# RoboCore_Light_sensor_bar.net
KiCad netlist of a schematic drawn in EAGLE
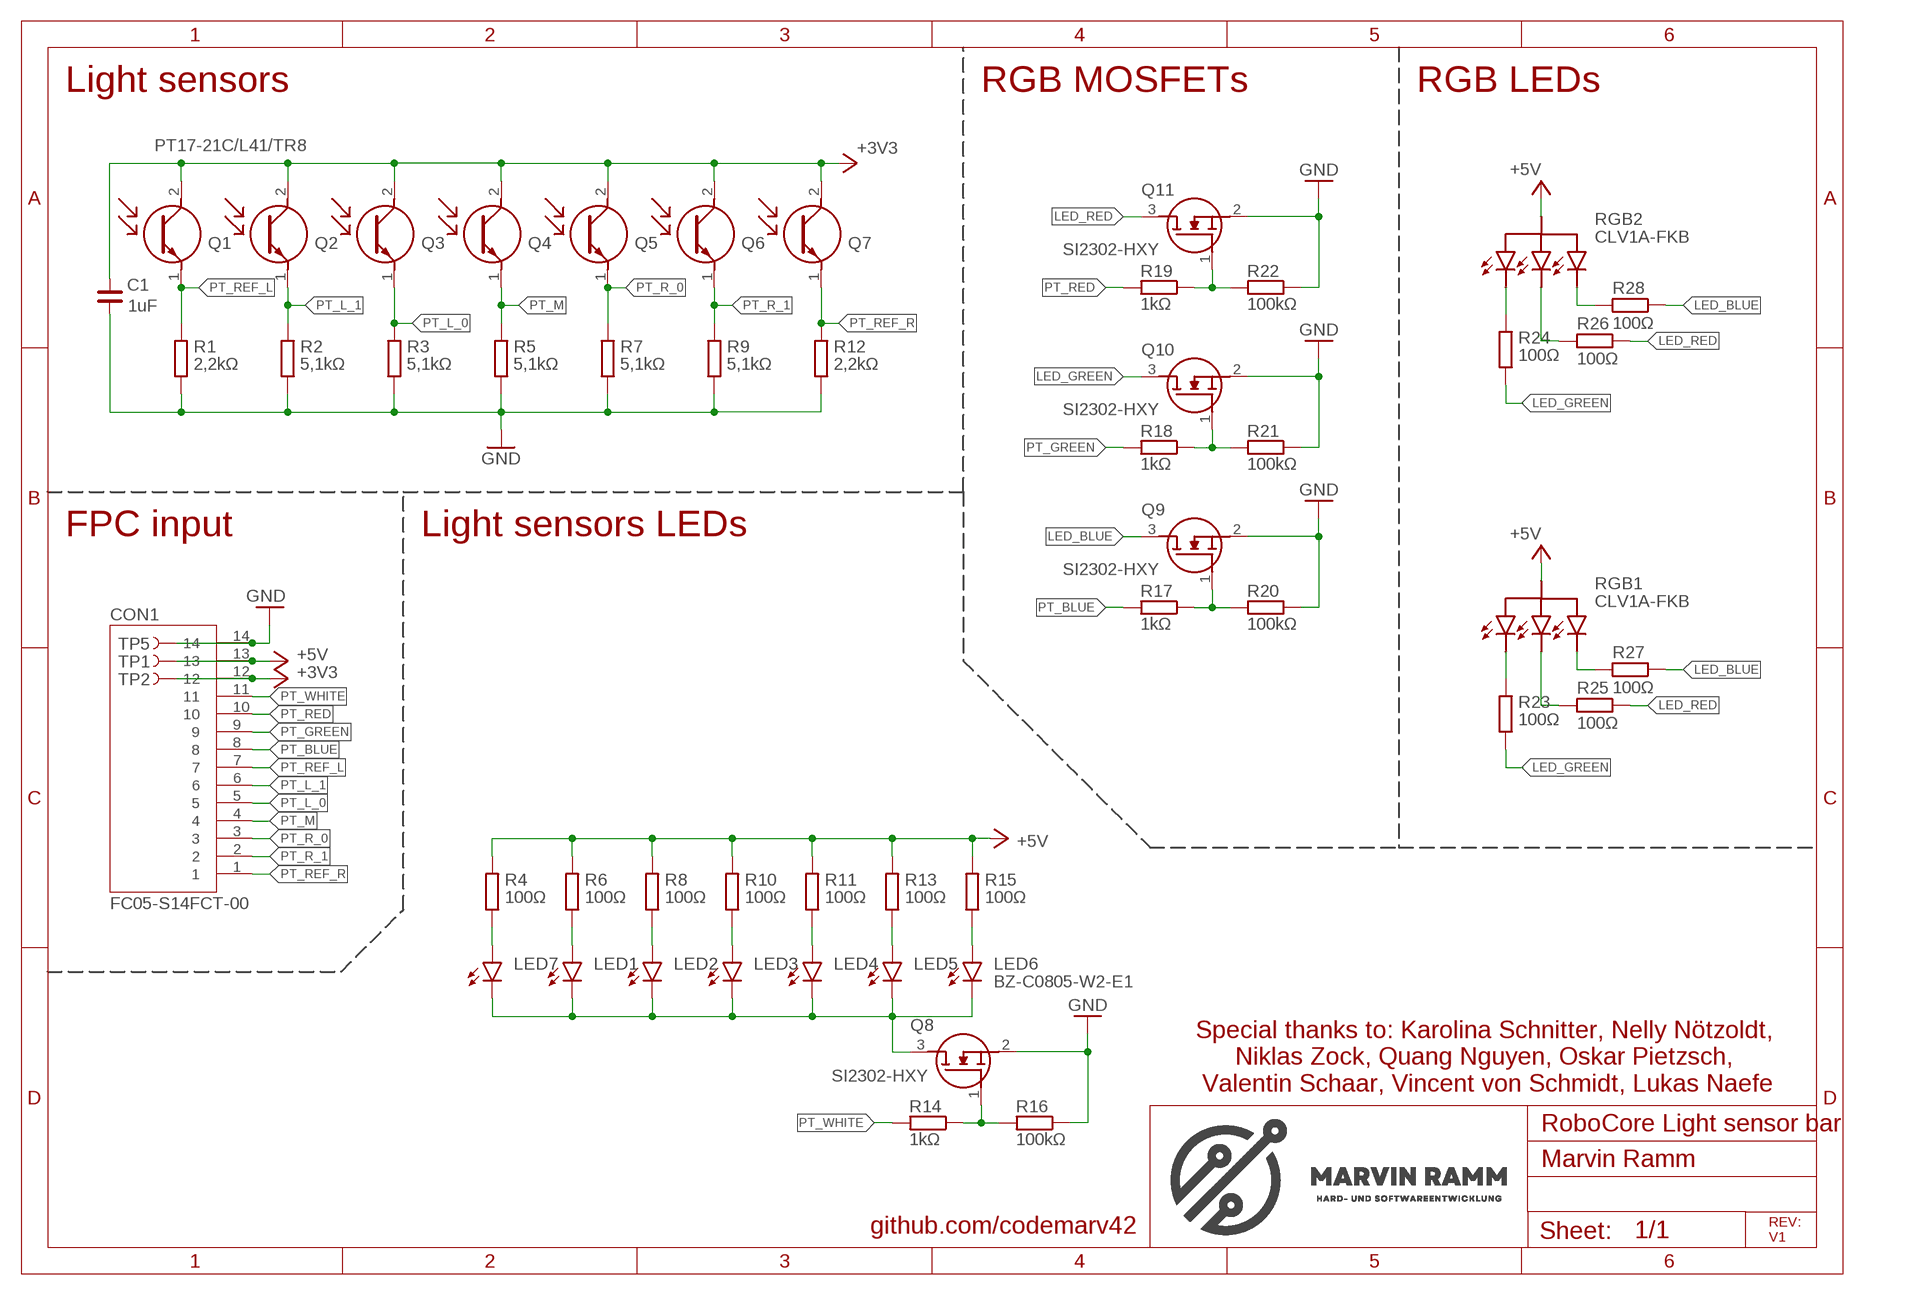
[diagram p0: schematic, sheet 1]

(export (version "E")
  (design (tool "Eeschema 10.0.6"))
  (components
    (comp (ref "C1")
      (value "1uF")
      (footprint "eagle-import:C0402")
      (libsource (lib "eagle-import") (part "C_0402"))
    )
    (comp (ref "CON1")
      (value "FC05-S14FCT-00")
      (footprint "eagle-import:FC05-S14FCT-00")
      (libsource (lib "eagle-import") (part "FC05-S14FCT-00"))
    )
    (comp (ref "LED1")
      (value "LEDCHIP-LED0805")
      (footprint "eagle-import:CHIP-LED0805")
      (libsource (lib "eagle-import") (part "LEDCHIP-LED0805"))
    )
    (comp (ref "LED2")
      (value "LEDCHIP-LED0805")
      (footprint "eagle-import:CHIP-LED0805")
      (libsource (lib "eagle-import") (part "LEDCHIP-LED0805"))
    )
    (comp (ref "LED3")
      (value "LEDCHIP-LED0805")
      (footprint "eagle-import:CHIP-LED0805")
      (libsource (lib "eagle-import") (part "LEDCHIP-LED0805"))
    )
    (comp (ref "LED4")
      (value "LEDCHIP-LED0805")
      (footprint "eagle-import:CHIP-LED0805")
      (libsource (lib "eagle-import") (part "LEDCHIP-LED0805"))
    )
    (comp (ref "LED5")
      (value "LEDCHIP-LED0805")
      (footprint "eagle-import:CHIP-LED0805")
      (libsource (lib "eagle-import") (part "LEDCHIP-LED0805"))
    )
    (comp (ref "LED6")
      (value "LEDCHIP-LED0805")
      (footprint "eagle-import:CHIP-LED0805")
      (libsource (lib "eagle-import") (part "LEDCHIP-LED0805"))
    )
    (comp (ref "LED7")
      (value "LEDCHIP-LED0805")
      (footprint "eagle-import:CHIP-LED0805")
      (libsource (lib "eagle-import") (part "LEDCHIP-LED0805"))
    )
    (comp (ref "Q1")
      (value "PT17-21C/L41/TR8")
      (footprint "eagle-import:0805")
      (libsource (lib "eagle-import") (part "PT17-21C/L41/TR8"))
    )
    (comp (ref "Q2")
      (value "PT17-21C/L41/TR8")
      (footprint "eagle-import:0805")
      (libsource (lib "eagle-import") (part "PT17-21C/L41/TR8"))
    )
    (comp (ref "Q3")
      (value "PT17-21C/L41/TR8")
      (footprint "eagle-import:0805")
      (libsource (lib "eagle-import") (part "PT17-21C/L41/TR8"))
    )
    (comp (ref "Q4")
      (value "PT17-21C/L41/TR8")
      (footprint "eagle-import:0805")
      (libsource (lib "eagle-import") (part "PT17-21C/L41/TR8"))
    )
    (comp (ref "Q5")
      (value "PT17-21C/L41/TR8")
      (footprint "eagle-import:0805")
      (libsource (lib "eagle-import") (part "PT17-21C/L41/TR8"))
    )
    (comp (ref "Q6")
      (value "PT17-21C/L41/TR8")
      (footprint "eagle-import:0805")
      (libsource (lib "eagle-import") (part "PT17-21C/L41/TR8"))
    )
    (comp (ref "Q7")
      (value "PT17-21C/L41/TR8")
      (footprint "eagle-import:0805")
      (libsource (lib "eagle-import") (part "PT17-21C/L41/TR8"))
    )
    (comp (ref "Q8")
      (value "SI2302DDS-T1-GE3")
      (footprint "eagle-import:SOT95P237X112-3N")
      (fields (field (name "MOUSER_PART_NUMBER") "78-SI2302DDS-T1-GE3"))
      (libsource (lib "eagle-import") (part "SI2302DDS-T1-GE3"))
    )
    (comp (ref "Q9")
      (value "SI2302DDS-T1-GE3")
      (footprint "eagle-import:SOT95P237X112-3N")
      (fields (field (name "MOUSER_PART_NUMBER") "78-SI2302DDS-T1-GE3"))
      (libsource (lib "eagle-import") (part "SI2302DDS-T1-GE3"))
    )
    (comp (ref "Q10")
      (value "SI2302DDS-T1-GE3")
      (footprint "eagle-import:SOT95P237X112-3N")
      (fields (field (name "MOUSER_PART_NUMBER") "78-SI2302DDS-T1-GE3"))
      (libsource (lib "eagle-import") (part "SI2302DDS-T1-GE3"))
    )
    (comp (ref "Q11")
      (value "SI2302DDS-T1-GE3")
      (footprint "eagle-import:SOT95P237X112-3N")
      (fields (field (name "MOUSER_PART_NUMBER") "78-SI2302DDS-T1-GE3"))
      (libsource (lib "eagle-import") (part "SI2302DDS-T1-GE3"))
    )
    (comp (ref "R1")
      (value "2,2kΩ")
      (footprint "eagle-import:R0402")
      (libsource (lib "eagle-import") (part "R_0402"))
    )
    (comp (ref "R2")
      (value "5,1kΩ")
      (footprint "eagle-import:R0402")
      (libsource (lib "eagle-import") (part "R_0402"))
    )
    (comp (ref "R3")
      (value "5,1kΩ")
      (footprint "eagle-import:R0402")
      (libsource (lib "eagle-import") (part "R_0402"))
    )
    (comp (ref "R4")
      (value "100Ω")
      (footprint "eagle-import:R0402")
      (libsource (lib "eagle-import") (part "R_0402"))
    )
    (comp (ref "R5")
      (value "5,1kΩ")
      (footprint "eagle-import:R0402")
      (libsource (lib "eagle-import") (part "R_0402"))
    )
    (comp (ref "R6")
      (value "100Ω")
      (footprint "eagle-import:R0402")
      (libsource (lib "eagle-import") (part "R_0402"))
    )
    (comp (ref "R7")
      (value "5,1kΩ")
      (footprint "eagle-import:R0402")
      (libsource (lib "eagle-import") (part "R_0402"))
    )
    (comp (ref "R8")
      (value "100Ω")
      (footprint "eagle-import:R0402")
      (libsource (lib "eagle-import") (part "R_0402"))
    )
    (comp (ref "R9")
      (value "5,1kΩ")
      (footprint "eagle-import:R0402")
      (libsource (lib "eagle-import") (part "R_0402"))
    )
    (comp (ref "R10")
      (value "100Ω")
      (footprint "eagle-import:R0402")
      (libsource (lib "eagle-import") (part "R_0402"))
    )
    (comp (ref "R11")
      (value "100Ω")
      (footprint "eagle-import:R0402")
      (libsource (lib "eagle-import") (part "R_0402"))
    )
    (comp (ref "R12")
      (value "2,2kΩ")
      (footprint "eagle-import:R0402")
      (libsource (lib "eagle-import") (part "R_0402"))
    )
    (comp (ref "R13")
      (value "100Ω")
      (footprint "eagle-import:R0402")
      (libsource (lib "eagle-import") (part "R_0402"))
    )
    (comp (ref "R14")
      (value "1kΩ")
      (footprint "eagle-import:R0402")
      (libsource (lib "eagle-import") (part "R_0402"))
    )
    (comp (ref "R15")
      (value "100Ω")
      (footprint "eagle-import:R0402")
      (libsource (lib "eagle-import") (part "R_0402"))
    )
    (comp (ref "R16")
      (value "100kΩ")
      (footprint "eagle-import:R0402")
      (libsource (lib "eagle-import") (part "R_0402"))
    )
    (comp (ref "R17")
      (value "1kΩ")
      (footprint "eagle-import:R0402")
      (libsource (lib "eagle-import") (part "R_0402"))
    )
    (comp (ref "R18")
      (value "1kΩ")
      (footprint "eagle-import:R0402")
      (libsource (lib "eagle-import") (part "R_0402"))
    )
    (comp (ref "R19")
      (value "1kΩ")
      (footprint "eagle-import:R0402")
      (libsource (lib "eagle-import") (part "R_0402"))
    )
    (comp (ref "R20")
      (value "100kΩ")
      (footprint "eagle-import:R0402")
      (libsource (lib "eagle-import") (part "R_0402"))
    )
    (comp (ref "R21")
      (value "100kΩ")
      (footprint "eagle-import:R0402")
      (libsource (lib "eagle-import") (part "R_0402"))
    )
    (comp (ref "R22")
      (value "100kΩ")
      (footprint "eagle-import:R0402")
      (libsource (lib "eagle-import") (part "R_0402"))
    )
    (comp (ref "R23")
      (value "100Ω")
      (footprint "eagle-import:R0402")
      (libsource (lib "eagle-import") (part "R_0402"))
    )
    (comp (ref "R24")
      (value "100Ω")
      (footprint "eagle-import:R0402")
      (libsource (lib "eagle-import") (part "R_0402"))
    )
    (comp (ref "R25")
      (value "100Ω")
      (footprint "eagle-import:R0402")
      (libsource (lib "eagle-import") (part "R_0402"))
    )
    (comp (ref "R26")
      (value "100Ω")
      (footprint "eagle-import:R0402")
      (libsource (lib "eagle-import") (part "R_0402"))
    )
    (comp (ref "R27")
      (value "100Ω")
      (footprint "eagle-import:R0402")
      (libsource (lib "eagle-import") (part "R_0402"))
    )
    (comp (ref "R28")
      (value "100Ω")
      (footprint "eagle-import:R0402")
      (libsource (lib "eagle-import") (part "R_0402"))
    )
    (comp (ref "RGB1")
      (value "RGBLED")
      (footprint "eagle-import:RGBLED")
      (libsource (lib "eagle-import") (part "RGBLED"))
    )
    (comp (ref "RGB2")
      (value "RGBLED")
      (footprint "eagle-import:RGBLED")
      (libsource (lib "eagle-import") (part "RGBLED"))
    )
    (comp (ref "TP1")
      (value "TEST-POINT3X5")
      (footprint "eagle-import:PAD.03X.05")
      (libsource (lib "eagle-import") (part "TEST-POINT3X5"))
    )
    (comp (ref "TP2")
      (value "TEST-POINT3X5")
      (footprint "eagle-import:PAD.03X.05")
      (libsource (lib "eagle-import") (part "TEST-POINT3X5"))
    )
    (comp (ref "TP5")
      (value "TEST-POINT3X5")
      (footprint "eagle-import:PAD.03X.05")
      (libsource (lib "eagle-import") (part "TEST-POINT3X5"))
    )
  )
  (nets
    (net (code "1") (name "+3V3") (class "Default")
      (node (ref "C1") (pin "2") (pinfunction "2_2") (pintype "passive"))
      (node (ref "CON1") (pin "12") (pinfunction "12_12") (pintype "bidirectional"))
      (node (ref "Q1") (pin "2") (pinfunction "C_2") (pintype "bidirectional"))
      (node (ref "Q2") (pin "2") (pinfunction "C_2") (pintype "bidirectional"))
      (node (ref "Q3") (pin "2") (pinfunction "C_2") (pintype "bidirectional"))
      (node (ref "Q4") (pin "2") (pinfunction "C_2") (pintype "bidirectional"))
      (node (ref "Q5") (pin "2") (pinfunction "C_2") (pintype "bidirectional"))
      (node (ref "Q6") (pin "2") (pinfunction "C_2") (pintype "bidirectional"))
      (node (ref "Q7") (pin "2") (pinfunction "C_2") (pintype "bidirectional"))
      (node (ref "TP2") (pin "1") (pinfunction "1_1") (pintype "bidirectional"))
    )
    (net (code "2") (name "+5V") (class "Default")
      (node (ref "CON1") (pin "13") (pinfunction "13_13") (pintype "bidirectional"))
      (node (ref "R10") (pin "1") (pinfunction "1_1") (pintype "passive"))
      (node (ref "R11") (pin "1") (pinfunction "1_1") (pintype "passive"))
      (node (ref "R13") (pin "1") (pinfunction "1_1") (pintype "passive"))
      (node (ref "R15") (pin "1") (pinfunction "1_1") (pintype "passive"))
      (node (ref "R4") (pin "1") (pinfunction "1_1") (pintype "passive"))
      (node (ref "R6") (pin "1") (pinfunction "1_1") (pintype "passive"))
      (node (ref "R8") (pin "1") (pinfunction "1_1") (pintype "passive"))
      (node (ref "RGB1") (pin "+5V") (pinfunction "+5V_+5V") (pintype "bidirectional"))
      (node (ref "RGB2") (pin "+5V") (pinfunction "+5V_+5V") (pintype "bidirectional"))
      (node (ref "TP1") (pin "1") (pinfunction "1_1") (pintype "bidirectional"))
    )
    (net (code "3") (name "GND") (class "Default")
      (node (ref "C1") (pin "1") (pinfunction "1_1") (pintype "passive"))
      (node (ref "CON1") (pin "14") (pinfunction "14_14") (pintype "bidirectional"))
      (node (ref "Q10") (pin "2") (pinfunction "S_2") (pintype "bidirectional"))
      (node (ref "Q11") (pin "2") (pinfunction "S_2") (pintype "bidirectional"))
      (node (ref "Q8") (pin "2") (pinfunction "S_2") (pintype "bidirectional"))
      (node (ref "Q9") (pin "2") (pinfunction "S_2") (pintype "bidirectional"))
      (node (ref "R1") (pin "2") (pinfunction "2_2") (pintype "passive"))
      (node (ref "R12") (pin "2") (pinfunction "2_2") (pintype "passive"))
      (node (ref "R16") (pin "2") (pinfunction "2_2") (pintype "passive"))
      (node (ref "R2") (pin "2") (pinfunction "2_2") (pintype "passive"))
      (node (ref "R20") (pin "2") (pinfunction "2_2") (pintype "passive"))
      (node (ref "R21") (pin "2") (pinfunction "2_2") (pintype "passive"))
      (node (ref "R22") (pin "2") (pinfunction "2_2") (pintype "passive"))
      (node (ref "R3") (pin "2") (pinfunction "2_2") (pintype "passive"))
      (node (ref "R5") (pin "2") (pinfunction "2_2") (pintype "passive"))
      (node (ref "R7") (pin "2") (pinfunction "2_2") (pintype "passive"))
      (node (ref "R9") (pin "2") (pinfunction "2_2") (pintype "passive"))
      (node (ref "TP5") (pin "1") (pinfunction "1_1") (pintype "bidirectional"))
    )
    (net (code "4") (name "LED_BLUE") (class "Default")
      (node (ref "Q9") (pin "3") (pinfunction "D_3") (pintype "bidirectional"))
      (node (ref "R27") (pin "2") (pinfunction "2_2") (pintype "passive"))
      (node (ref "R28") (pin "2") (pinfunction "2_2") (pintype "passive"))
    )
    (net (code "5") (name "LED_GREEN") (class "Default")
      (node (ref "Q10") (pin "3") (pinfunction "D_3") (pintype "bidirectional"))
      (node (ref "R23") (pin "2") (pinfunction "2_2") (pintype "passive"))
      (node (ref "R24") (pin "2") (pinfunction "2_2") (pintype "passive"))
    )
    (net (code "6") (name "LED_RED") (class "Default")
      (node (ref "Q11") (pin "3") (pinfunction "D_3") (pintype "bidirectional"))
      (node (ref "R25") (pin "2") (pinfunction "2_2") (pintype "passive"))
      (node (ref "R26") (pin "2") (pinfunction "2_2") (pintype "passive"))
    )
    (net (code "7") (name "Net-(LED1-PadA)") (class "Default")
      (node (ref "LED1") (pin "A") (pinfunction "A_A") (pintype "passive"))
      (node (ref "R6") (pin "2") (pinfunction "2_2") (pintype "passive"))
    )
    (net (code "8") (name "Net-(LED2-PadA)") (class "Default")
      (node (ref "LED2") (pin "A") (pinfunction "A_A") (pintype "passive"))
      (node (ref "R8") (pin "2") (pinfunction "2_2") (pintype "passive"))
    )
    (net (code "9") (name "Net-(LED3-PadA)") (class "Default")
      (node (ref "LED3") (pin "A") (pinfunction "A_A") (pintype "passive"))
      (node (ref "R10") (pin "2") (pinfunction "2_2") (pintype "passive"))
    )
    (net (code "10") (name "Net-(LED4-PadA)") (class "Default")
      (node (ref "LED4") (pin "A") (pinfunction "A_A") (pintype "passive"))
      (node (ref "R11") (pin "2") (pinfunction "2_2") (pintype "passive"))
    )
    (net (code "11") (name "Net-(LED5-PadA)") (class "Default")
      (node (ref "LED5") (pin "A") (pinfunction "A_A") (pintype "passive"))
      (node (ref "R13") (pin "2") (pinfunction "2_2") (pintype "passive"))
    )
    (net (code "12") (name "Net-(LED6-PadA)") (class "Default")
      (node (ref "LED6") (pin "A") (pinfunction "A_A") (pintype "passive"))
      (node (ref "R15") (pin "2") (pinfunction "2_2") (pintype "passive"))
    )
    (net (code "13") (name "Net-(LED7-PadA)") (class "Default")
      (node (ref "LED7") (pin "A") (pinfunction "A_A") (pintype "passive"))
      (node (ref "R4") (pin "2") (pinfunction "2_2") (pintype "passive"))
    )
    (net (code "14") (name "Net-(Q8-D)") (class "Default")
      (node (ref "LED1") (pin "C") (pinfunction "C_C") (pintype "passive"))
      (node (ref "LED2") (pin "C") (pinfunction "C_C") (pintype "passive"))
      (node (ref "LED3") (pin "C") (pinfunction "C_C") (pintype "passive"))
      (node (ref "LED4") (pin "C") (pinfunction "C_C") (pintype "passive"))
      (node (ref "LED5") (pin "C") (pinfunction "C_C") (pintype "passive"))
      (node (ref "LED6") (pin "C") (pinfunction "C_C") (pintype "passive"))
      (node (ref "LED7") (pin "C") (pinfunction "C_C") (pintype "passive"))
      (node (ref "Q8") (pin "3") (pinfunction "D_3") (pintype "bidirectional"))
    )
    (net (code "15") (name "Net-(Q8-G)") (class "Default")
      (node (ref "Q8") (pin "1") (pinfunction "G_1") (pintype "bidirectional"))
      (node (ref "R14") (pin "2") (pinfunction "2_2") (pintype "passive"))
      (node (ref "R16") (pin "1") (pinfunction "1_1") (pintype "passive"))
    )
    (net (code "16") (name "Net-(Q9-G)") (class "Default")
      (node (ref "Q9") (pin "1") (pinfunction "G_1") (pintype "bidirectional"))
      (node (ref "R17") (pin "2") (pinfunction "2_2") (pintype "passive"))
      (node (ref "R20") (pin "1") (pinfunction "1_1") (pintype "passive"))
    )
    (net (code "17") (name "Net-(Q10-G)") (class "Default")
      (node (ref "Q10") (pin "1") (pinfunction "G_1") (pintype "bidirectional"))
      (node (ref "R18") (pin "2") (pinfunction "2_2") (pintype "passive"))
      (node (ref "R21") (pin "1") (pinfunction "1_1") (pintype "passive"))
    )
    (net (code "18") (name "Net-(Q11-G)") (class "Default")
      (node (ref "Q11") (pin "1") (pinfunction "G_1") (pintype "bidirectional"))
      (node (ref "R19") (pin "2") (pinfunction "2_2") (pintype "passive"))
      (node (ref "R22") (pin "1") (pinfunction "1_1") (pintype "passive"))
    )
    (net (code "19") (name "Net-(R23-Pad1)") (class "Default")
      (node (ref "R23") (pin "1") (pinfunction "1_1") (pintype "passive"))
      (node (ref "RGB1") (pin "P3") (pinfunction "P3_P3") (pintype "bidirectional"))
    )
    (net (code "20") (name "Net-(R24-Pad1)") (class "Default")
      (node (ref "R24") (pin "1") (pinfunction "1_1") (pintype "passive"))
      (node (ref "RGB2") (pin "P3") (pinfunction "P3_P3") (pintype "bidirectional"))
    )
    (net (code "21") (name "Net-(R25-Pad1)") (class "Default")
      (node (ref "R25") (pin "1") (pinfunction "1_1") (pintype "passive"))
      (node (ref "RGB1") (pin "P2") (pinfunction "P2_P2") (pintype "bidirectional"))
    )
    (net (code "22") (name "Net-(R26-Pad1)") (class "Default")
      (node (ref "R26") (pin "1") (pinfunction "1_1") (pintype "passive"))
      (node (ref "RGB2") (pin "P2") (pinfunction "P2_P2") (pintype "bidirectional"))
    )
    (net (code "23") (name "Net-(R27-Pad1)") (class "Default")
      (node (ref "R27") (pin "1") (pinfunction "1_1") (pintype "passive"))
      (node (ref "RGB1") (pin "P1") (pinfunction "P1_P1") (pintype "bidirectional"))
    )
    (net (code "24") (name "Net-(R28-Pad1)") (class "Default")
      (node (ref "R28") (pin "1") (pinfunction "1_1") (pintype "passive"))
      (node (ref "RGB2") (pin "P1") (pinfunction "P1_P1") (pintype "bidirectional"))
    )
    (net (code "25") (name "PT_BLUE") (class "Default")
      (node (ref "CON1") (pin "8") (pinfunction "8_8") (pintype "bidirectional"))
      (node (ref "R17") (pin "1") (pinfunction "1_1") (pintype "passive"))
    )
    (net (code "26") (name "PT_GREEN") (class "Default")
      (node (ref "CON1") (pin "9") (pinfunction "9_9") (pintype "bidirectional"))
      (node (ref "R18") (pin "1") (pinfunction "1_1") (pintype "passive"))
    )
    (net (code "27") (name "PT_L_0") (class "Default")
      (node (ref "CON1") (pin "5") (pinfunction "5_5") (pintype "bidirectional"))
      (node (ref "Q3") (pin "1") (pinfunction "E_1") (pintype "bidirectional"))
      (node (ref "R3") (pin "1") (pinfunction "1_1") (pintype "passive"))
    )
    (net (code "28") (name "PT_L_1") (class "Default")
      (node (ref "CON1") (pin "6") (pinfunction "6_6") (pintype "bidirectional"))
      (node (ref "Q2") (pin "1") (pinfunction "E_1") (pintype "bidirectional"))
      (node (ref "R2") (pin "1") (pinfunction "1_1") (pintype "passive"))
    )
    (net (code "29") (name "PT_M") (class "Default")
      (node (ref "CON1") (pin "4") (pinfunction "4_4") (pintype "bidirectional"))
      (node (ref "Q4") (pin "1") (pinfunction "E_1") (pintype "bidirectional"))
      (node (ref "R5") (pin "1") (pinfunction "1_1") (pintype "passive"))
    )
    (net (code "30") (name "PT_RED") (class "Default")
      (node (ref "CON1") (pin "10") (pinfunction "10_10") (pintype "bidirectional"))
      (node (ref "R19") (pin "1") (pinfunction "1_1") (pintype "passive"))
    )
    (net (code "31") (name "PT_REF_L") (class "Default")
      (node (ref "CON1") (pin "7") (pinfunction "7_7") (pintype "bidirectional"))
      (node (ref "Q1") (pin "1") (pinfunction "E_1") (pintype "bidirectional"))
      (node (ref "R1") (pin "1") (pinfunction "1_1") (pintype "passive"))
    )
    (net (code "32") (name "PT_REF_R") (class "Default")
      (node (ref "CON1") (pin "1") (pinfunction "1_1") (pintype "bidirectional"))
      (node (ref "Q7") (pin "1") (pinfunction "E_1") (pintype "bidirectional"))
      (node (ref "R12") (pin "1") (pinfunction "1_1") (pintype "passive"))
    )
    (net (code "33") (name "PT_R_0") (class "Default")
      (node (ref "CON1") (pin "3") (pinfunction "3_3") (pintype "bidirectional"))
      (node (ref "Q5") (pin "1") (pinfunction "E_1") (pintype "bidirectional"))
      (node (ref "R7") (pin "1") (pinfunction "1_1") (pintype "passive"))
    )
    (net (code "34") (name "PT_R_1") (class "Default")
      (node (ref "CON1") (pin "2") (pinfunction "2_2") (pintype "bidirectional"))
      (node (ref "Q6") (pin "1") (pinfunction "E_1") (pintype "bidirectional"))
      (node (ref "R9") (pin "1") (pinfunction "1_1") (pintype "passive"))
    )
    (net (code "35") (name "PT_WHITE") (class "Default")
      (node (ref "CON1") (pin "11") (pinfunction "11_11") (pintype "bidirectional"))
      (node (ref "R14") (pin "1") (pinfunction "1_1") (pintype "passive"))
    )
  )
)
